# RFM.net
KiCad netlist of a schematic drawn in EAGLE
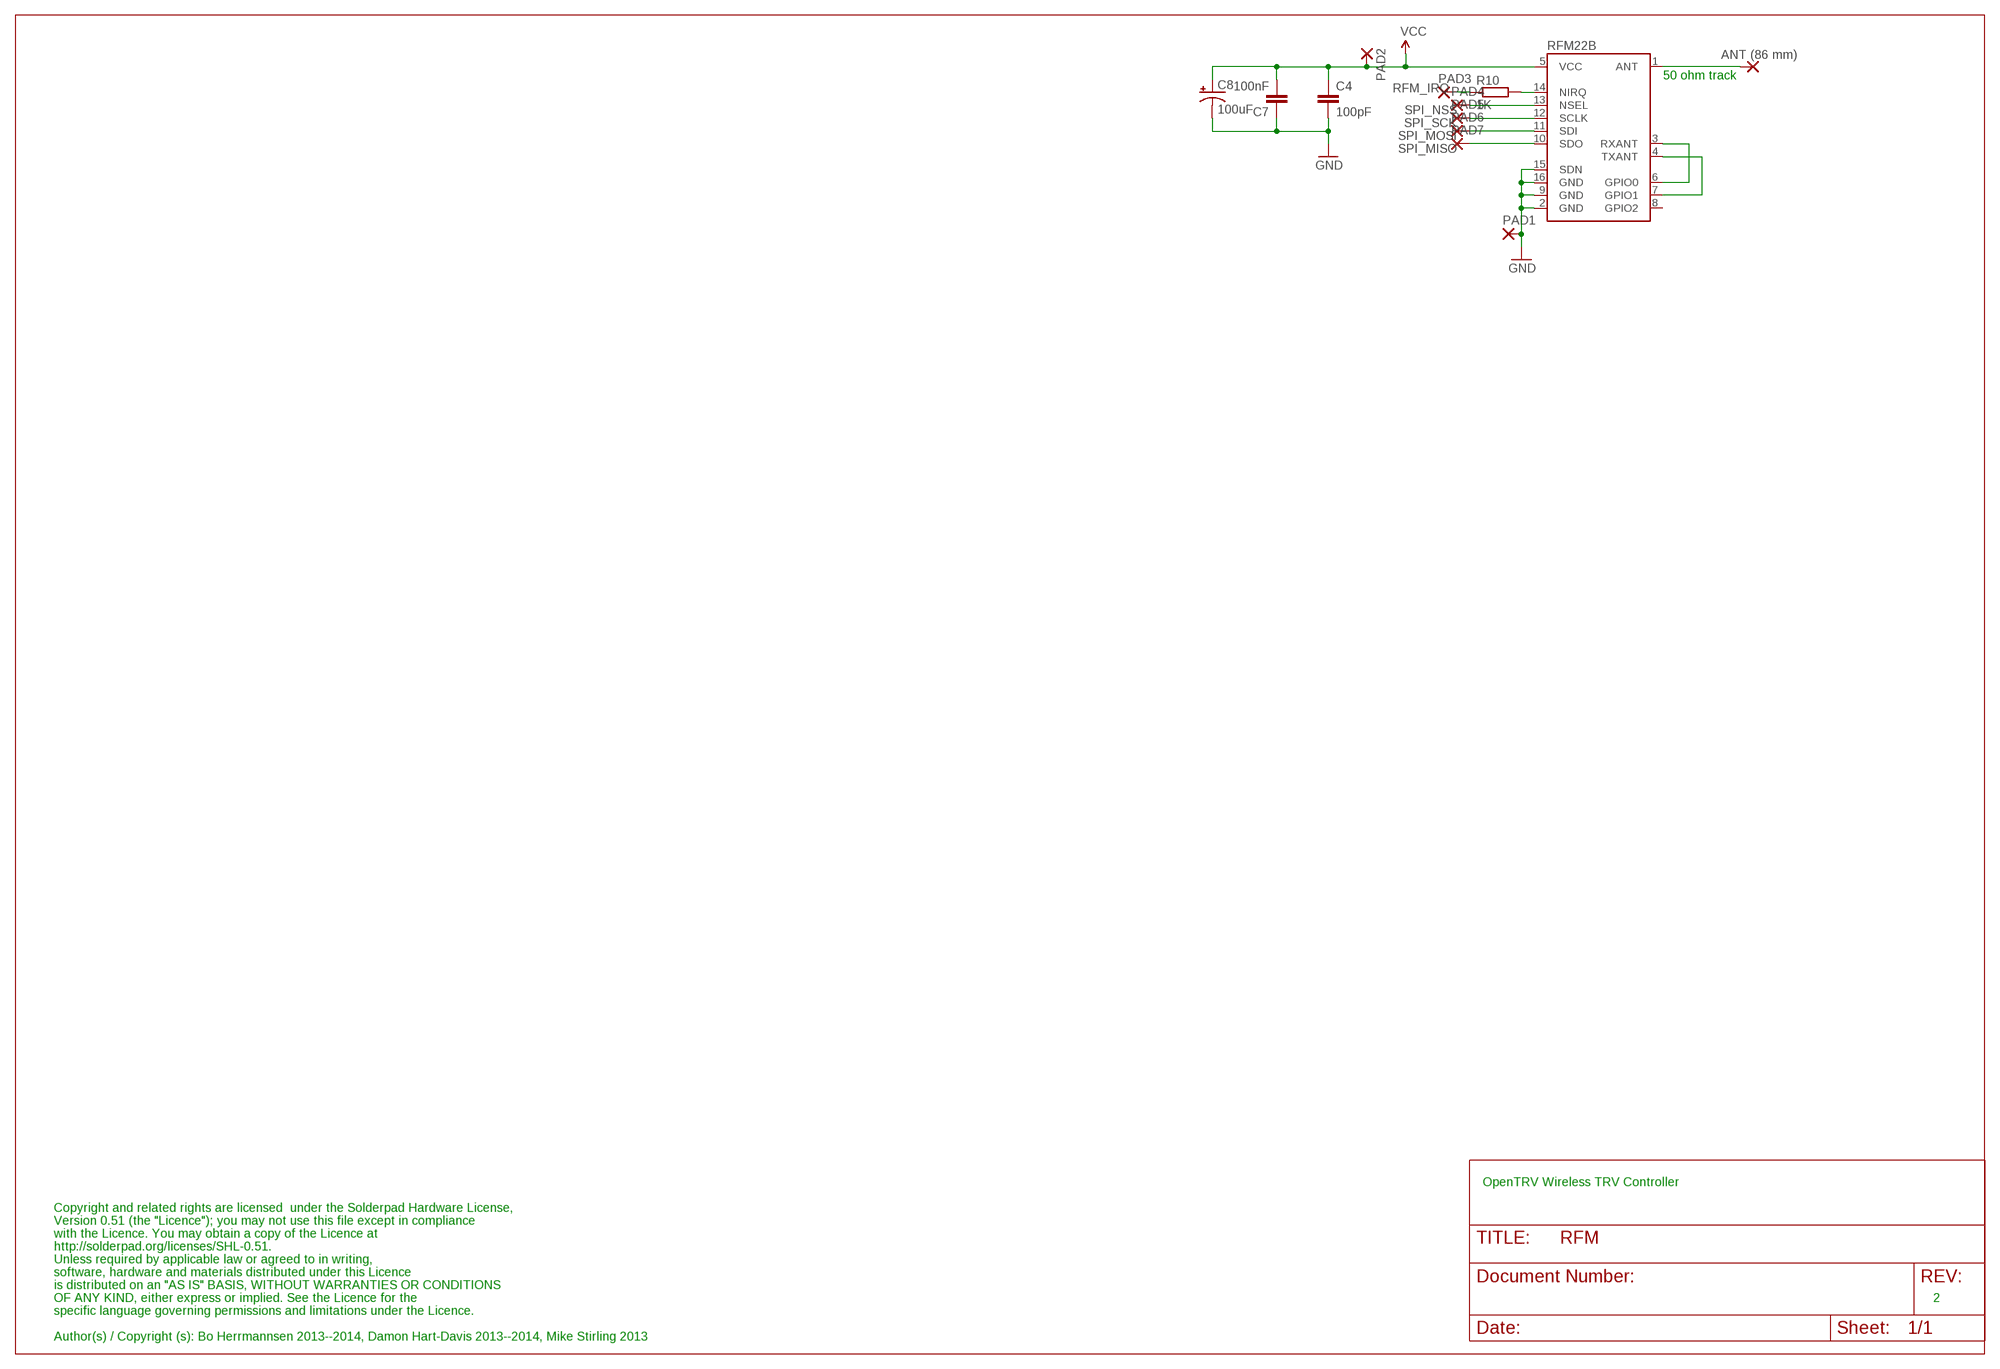
[diagram p0: schematic, sheet 1]

(export (version "E")
  (design (tool "Eeschema 10.0.6"))
  (components
    (comp (ref "ANT")
      (value "ANT (86 mm)")
      (footprint "eagle-import:2,15_1,0")
      (libsource (lib "eagle-import") (part "2,15/1,0"))
    )
    (comp (ref "C4")
      (value "100pF")
      (footprint "eagle-import:0603-CAP")
      (libsource (lib "eagle-import") (part "CAP0603-CAP"))
    )
    (comp (ref "C7")
      (value "100nF")
      (footprint "eagle-import:0603-CAP")
      (libsource (lib "eagle-import") (part "CAP0603-CAP"))
    )
    (comp (ref "C8")
      (value "100uF")
      (footprint "eagle-import:EIA3216")
      (libsource (lib "eagle-import") (part "CAP_POL1206"))
    )
    (comp (ref "PAD1")
      (value "1,6/0,8")
      (footprint "eagle-import:1,6_0,8")
      (libsource (lib "eagle-import") (part "1,6/0,8"))
    )
    (comp (ref "PAD2")
      (value "1,6/0,8")
      (footprint "eagle-import:1,6_0,8")
      (libsource (lib "eagle-import") (part "1,6/0,8"))
    )
    (comp (ref "PAD3")
      (value "1,6/0,8")
      (footprint "eagle-import:1,6_0,8")
      (libsource (lib "eagle-import") (part "1,6/0,8"))
    )
    (comp (ref "PAD4")
      (value "1,6/0,8")
      (footprint "eagle-import:1,6_0,8")
      (libsource (lib "eagle-import") (part "1,6/0,8"))
    )
    (comp (ref "PAD5")
      (value "1,6/0,8")
      (footprint "eagle-import:1,6_0,8")
      (libsource (lib "eagle-import") (part "1,6/0,8"))
    )
    (comp (ref "PAD6")
      (value "1,6/0,8")
      (footprint "eagle-import:1,6_0,8")
      (libsource (lib "eagle-import") (part "1,6/0,8"))
    )
    (comp (ref "PAD7")
      (value "1,6/0,8")
      (footprint "eagle-import:1,6_0,8")
      (libsource (lib "eagle-import") (part "1,6/0,8"))
    )
    (comp (ref "R10")
      (value "1K")
      (footprint "eagle-import:R0603")
      (libsource (lib "eagle-import") (part "R-EU_R0603"))
    )
    (comp (ref "RFM22B")
      (value "RFM22SMD")
      (footprint "eagle-import:RFM22-XXX-S2")
      (libsource (lib "eagle-import") (part "RFM22SMD"))
    )
  )
  (nets
    (net (code "1") (name "/RFM_IRQ") (class "Default")
      (node (ref "PAD3") (pin "1") (pinfunction "P_1") (pintype "passive"))
      (node (ref "R10") (pin "1") (pinfunction "1_1") (pintype "passive"))
    )
    (net (code "2") (name "/SPI_MISO") (class "Default")
      (node (ref "PAD7") (pin "1") (pinfunction "P_1") (pintype "passive"))
      (node (ref "RFM22B") (pin "10") (pinfunction "SDO_10") (pintype "output"))
    )
    (net (code "3") (name "/SPI_MOSI") (class "Default")
      (node (ref "PAD6") (pin "1") (pinfunction "P_1") (pintype "passive"))
      (node (ref "RFM22B") (pin "11") (pinfunction "SDI_11") (pintype "input"))
    )
    (net (code "4") (name "/SPI_NSS") (class "Default")
      (node (ref "PAD4") (pin "1") (pinfunction "P_1") (pintype "passive"))
      (node (ref "RFM22B") (pin "13") (pinfunction "NSEL_13") (pintype "input"))
    )
    (net (code "5") (name "/SPI_SCK") (class "Default")
      (node (ref "PAD5") (pin "1") (pinfunction "P_1") (pintype "passive"))
      (node (ref "RFM22B") (pin "12") (pinfunction "SCLK_12") (pintype "input"))
    )
    (net (code "6") (name "GND") (class "Default")
      (node (ref "C4") (pin "2") (pinfunction "2_2") (pintype "passive"))
      (node (ref "C7") (pin "1") (pinfunction "1_1") (pintype "passive"))
      (node (ref "C8") (pin "C") (pinfunction "-_C") (pintype "passive"))
      (node (ref "PAD1") (pin "1") (pinfunction "P_1") (pintype "passive"))
      (node (ref "RFM22B") (pin "15") (pinfunction "SDN_15") (pintype "input"))
      (node (ref "RFM22B") (pin "16") (pinfunction "GND_16") (pintype "power_in"))
      (node (ref "RFM22B") (pin "2") (pinfunction "GND_2") (pintype "power_in"))
      (node (ref "RFM22B") (pin "9") (pinfunction "GND_9") (pintype "power_in"))
    )
    (net (code "7") (name "Net-(ANT-P)") (class "Default")
      (node (ref "ANT") (pin "1") (pinfunction "P_1") (pintype "passive"))
      (node (ref "RFM22B") (pin "1") (pinfunction "ANT_1") (pintype "bidirectional"))
    )
    (net (code "8") (name "Net-(RFM22B-GPIO0)") (class "Default")
      (node (ref "RFM22B") (pin "3") (pinfunction "RXANT_3") (pintype "input"))
      (node (ref "RFM22B") (pin "6") (pinfunction "GPIO0_6") (pintype "bidirectional"))
    )
    (net (code "9") (name "Net-(RFM22B-GPIO1)") (class "Default")
      (node (ref "RFM22B") (pin "4") (pinfunction "TXANT_4") (pintype "input"))
      (node (ref "RFM22B") (pin "7") (pinfunction "GPIO1_7") (pintype "bidirectional"))
    )
    (net (code "10") (name "Net-(RFM22B-NIRQ)") (class "Default")
      (node (ref "R10") (pin "2") (pinfunction "2_2") (pintype "passive"))
      (node (ref "RFM22B") (pin "14") (pinfunction "NIRQ_14") (pintype "output"))
    )
    (net (code "11") (name "VCC") (class "Default")
      (node (ref "C4") (pin "1") (pinfunction "1_1") (pintype "passive"))
      (node (ref "C7") (pin "2") (pinfunction "2_2") (pintype "passive"))
      (node (ref "C8") (pin "A") (pinfunction "+_A") (pintype "passive"))
      (node (ref "PAD2") (pin "1") (pinfunction "P_1") (pintype "passive"))
      (node (ref "RFM22B") (pin "5") (pinfunction "VCC_5") (pintype "bidirectional"))
    )
    (net (code "12") (name "unconnected-(RFM22B-GPIO2-Pad8)") (class "Default")
      (node (ref "RFM22B") (pin "8") (pinfunction "GPIO2_8") (pintype "bidirectional"))
    )
  )
)
